# board.net
KiCad netlist of a schematic drawn in EAGLE
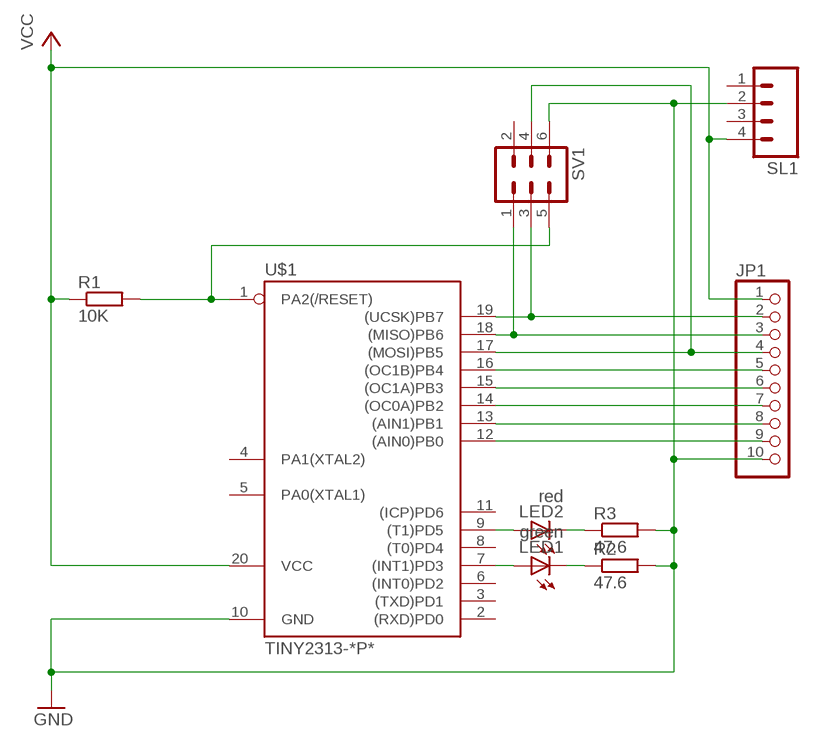
[diagram p0: schematic, sheet 1]

(export (version "E")
  (design (tool "Eeschema 10.0.6"))
  (components
    (comp (ref "JP1")
      (value "PINHD-1X10")
      (footprint "eagle-import:1X10")
      (libsource (lib "eagle-import") (part "PINHD-1X10"))
    )
    (comp (ref "LED1")
      (value "green")
      (footprint "eagle-import:LED3MM")
      (libsource (lib "eagle-import") (part "LED3MM"))
    )
    (comp (ref "LED2")
      (value "red")
      (footprint "eagle-import:LED3MM")
      (libsource (lib "eagle-import") (part "LED3MM"))
    )
    (comp (ref "R1")
      (value "10K")
      (footprint "eagle-import:0207_2V")
      (libsource (lib "eagle-import") (part "R-EU_0207/2V"))
    )
    (comp (ref "R2")
      (value "47.6")
      (footprint "eagle-import:0207_2V")
      (libsource (lib "eagle-import") (part "R-EU_0207/2V"))
    )
    (comp (ref "R3")
      (value "47.6")
      (footprint "eagle-import:0207_2V")
      (libsource (lib "eagle-import") (part "R-EU_0207/2V"))
    )
    (comp (ref "SL1")
      (value "M04")
      (footprint "eagle-import:04P")
      (libsource (lib "eagle-import") (part "M04"))
    )
    (comp (ref "SV1")
      (value "ML6")
      (footprint "eagle-import:ML6")
      (libsource (lib "eagle-import") (part "ML6"))
    )
    (comp (ref "U$1")
      (value "TINY2313-*P*")
      (footprint "eagle-import:DIL20")
      (libsource (lib "eagle-import") (part "TINY2313-P"))
    )
  )
  (nets
    (net (code "1") (name "GND") (class "Default")
      (node (ref "JP1") (pin "10") (pinfunction "10_10") (pintype "passive"))
      (node (ref "R2") (pin "2") (pinfunction "2_2") (pintype "passive"))
      (node (ref "R3") (pin "2") (pinfunction "2_2") (pintype "passive"))
      (node (ref "SL1") (pin "2") (pinfunction "2_2") (pintype "passive"))
      (node (ref "SV1") (pin "6") (pinfunction "6_6") (pintype "passive"))
      (node (ref "U$1") (pin "10") (pinfunction "GND_10") (pintype "power_in"))
    )
    (net (code "2") (name "Net-(LED1-C)") (class "Default")
      (node (ref "LED1") (pin "K") (pinfunction "C_K") (pintype "passive"))
      (node (ref "R2") (pin "1") (pinfunction "1_1") (pintype "passive"))
    )
    (net (code "3") (name "Net-(LED2-C)") (class "Default")
      (node (ref "LED2") (pin "K") (pinfunction "C_K") (pintype "passive"))
      (node (ref "R3") (pin "1") (pinfunction "1_1") (pintype "passive"))
    )
    (net (code "4") (name "Net-(U$1-(AIN0)PB0)") (class "Default")
      (node (ref "JP1") (pin "9") (pinfunction "9_9") (pintype "passive"))
      (node (ref "U$1") (pin "12") (pinfunction "(AIN0)PB0_12") (pintype "bidirectional"))
    )
    (net (code "5") (name "Net-(U$1-(AIN1)PB1)") (class "Default")
      (node (ref "JP1") (pin "8") (pinfunction "8_8") (pintype "passive"))
      (node (ref "U$1") (pin "13") (pinfunction "(AIN1)PB1_13") (pintype "bidirectional"))
    )
    (net (code "6") (name "Net-(U$1-(INT1)PD3)") (class "Default")
      (node (ref "LED1") (pin "A") (pinfunction "A_A") (pintype "passive"))
      (node (ref "U$1") (pin "7") (pinfunction "(INT1)PD3_7") (pintype "bidirectional"))
    )
    (net (code "7") (name "Net-(U$1-(MISO)PB6)") (class "Default")
      (node (ref "JP1") (pin "3") (pinfunction "3_3") (pintype "passive"))
      (node (ref "SV1") (pin "1") (pinfunction "1_1") (pintype "passive"))
      (node (ref "U$1") (pin "18") (pinfunction "(MISO)PB6_18") (pintype "bidirectional"))
    )
    (net (code "8") (name "Net-(U$1-(MOSI)PB5)") (class "Default")
      (node (ref "JP1") (pin "4") (pinfunction "4_4") (pintype "passive"))
      (node (ref "SV1") (pin "4") (pinfunction "4_4") (pintype "passive"))
      (node (ref "U$1") (pin "17") (pinfunction "(MOSI)PB5_17") (pintype "bidirectional"))
    )
    (net (code "9") (name "Net-(U$1-(OC0A)PB2)") (class "Default")
      (node (ref "JP1") (pin "7") (pinfunction "7_7") (pintype "passive"))
      (node (ref "U$1") (pin "14") (pinfunction "(OC0A)PB2_14") (pintype "bidirectional"))
    )
    (net (code "10") (name "Net-(U$1-(OC1A)PB3)") (class "Default")
      (node (ref "JP1") (pin "6") (pinfunction "6_6") (pintype "passive"))
      (node (ref "U$1") (pin "15") (pinfunction "(OC1A)PB3_15") (pintype "bidirectional"))
    )
    (net (code "11") (name "Net-(U$1-(OC1B)PB4)") (class "Default")
      (node (ref "JP1") (pin "5") (pinfunction "5_5") (pintype "passive"))
      (node (ref "U$1") (pin "16") (pinfunction "(OC1B)PB4_16") (pintype "bidirectional"))
    )
    (net (code "12") (name "Net-(U$1-(T1)PD5)") (class "Default")
      (node (ref "LED2") (pin "A") (pinfunction "A_A") (pintype "passive"))
      (node (ref "U$1") (pin "9") (pinfunction "(T1)PD5_9") (pintype "bidirectional"))
    )
    (net (code "13") (name "Net-(U$1-(UCSK)PB7)") (class "Default")
      (node (ref "JP1") (pin "2") (pinfunction "2_2") (pintype "passive"))
      (node (ref "SV1") (pin "3") (pinfunction "3_3") (pintype "passive"))
      (node (ref "U$1") (pin "19") (pinfunction "(UCSK)PB7_19") (pintype "bidirectional"))
    )
    (net (code "14") (name "Net-(U$1-PA2({slash}RESET))") (class "Default")
      (node (ref "R1") (pin "2") (pinfunction "2_2") (pintype "passive"))
      (node (ref "SV1") (pin "5") (pinfunction "5_5") (pintype "passive"))
      (node (ref "U$1") (pin "1") (pinfunction "PA2(/RESET)_1") (pintype "input"))
    )
    (net (code "15") (name "VCC") (class "Default")
      (node (ref "JP1") (pin "1") (pinfunction "1_1") (pintype "passive"))
      (node (ref "R1") (pin "1") (pinfunction "1_1") (pintype "passive"))
      (node (ref "SL1") (pin "4") (pinfunction "4_4") (pintype "passive"))
      (node (ref "U$1") (pin "20") (pinfunction "VCC_20") (pintype "power_in"))
    )
    (net (code "16") (name "unconnected-(SL1-Pad1)") (class "Default")
      (node (ref "SL1") (pin "1") (pinfunction "1_1") (pintype "passive"))
    )
    (net (code "17") (name "unconnected-(SL1-Pad3)") (class "Default")
      (node (ref "SL1") (pin "3") (pinfunction "3_3") (pintype "passive"))
    )
    (net (code "18") (name "unconnected-(SV1-Pad2)") (class "Default")
      (node (ref "SV1") (pin "2") (pinfunction "2_2") (pintype "passive"))
    )
    (net (code "19") (name "unconnected-(U$1-(ICP)PD6-Pad11)") (class "Default")
      (node (ref "U$1") (pin "11") (pinfunction "(ICP)PD6_11") (pintype "bidirectional"))
    )
    (net (code "20") (name "unconnected-(U$1-(INT0)PD2-Pad6)") (class "Default")
      (node (ref "U$1") (pin "6") (pinfunction "(INT0)PD2_6") (pintype "bidirectional"))
    )
    (net (code "21") (name "unconnected-(U$1-(RXD)PD0-Pad2)") (class "Default")
      (node (ref "U$1") (pin "2") (pinfunction "(RXD)PD0_2") (pintype "bidirectional"))
    )
    (net (code "22") (name "unconnected-(U$1-(T0)PD4-Pad8)") (class "Default")
      (node (ref "U$1") (pin "8") (pinfunction "(T0)PD4_8") (pintype "bidirectional"))
    )
    (net (code "23") (name "unconnected-(U$1-(TXD)PD1-Pad3)") (class "Default")
      (node (ref "U$1") (pin "3") (pinfunction "(TXD)PD1_3") (pintype "bidirectional"))
    )
    (net (code "24") (name "unconnected-(U$1-PA0(XTAL1)-Pad5)") (class "Default")
      (node (ref "U$1") (pin "5") (pinfunction "PA0(XTAL1)_5") (pintype "bidirectional"))
    )
    (net (code "25") (name "unconnected-(U$1-PA1(XTAL2)-Pad4)") (class "Default")
      (node (ref "U$1") (pin "4") (pinfunction "PA1(XTAL2)_4") (pintype "bidirectional"))
    )
  )
)
